# YW_001.net
KiCad netlist of a schematic drawn in Altium Designer
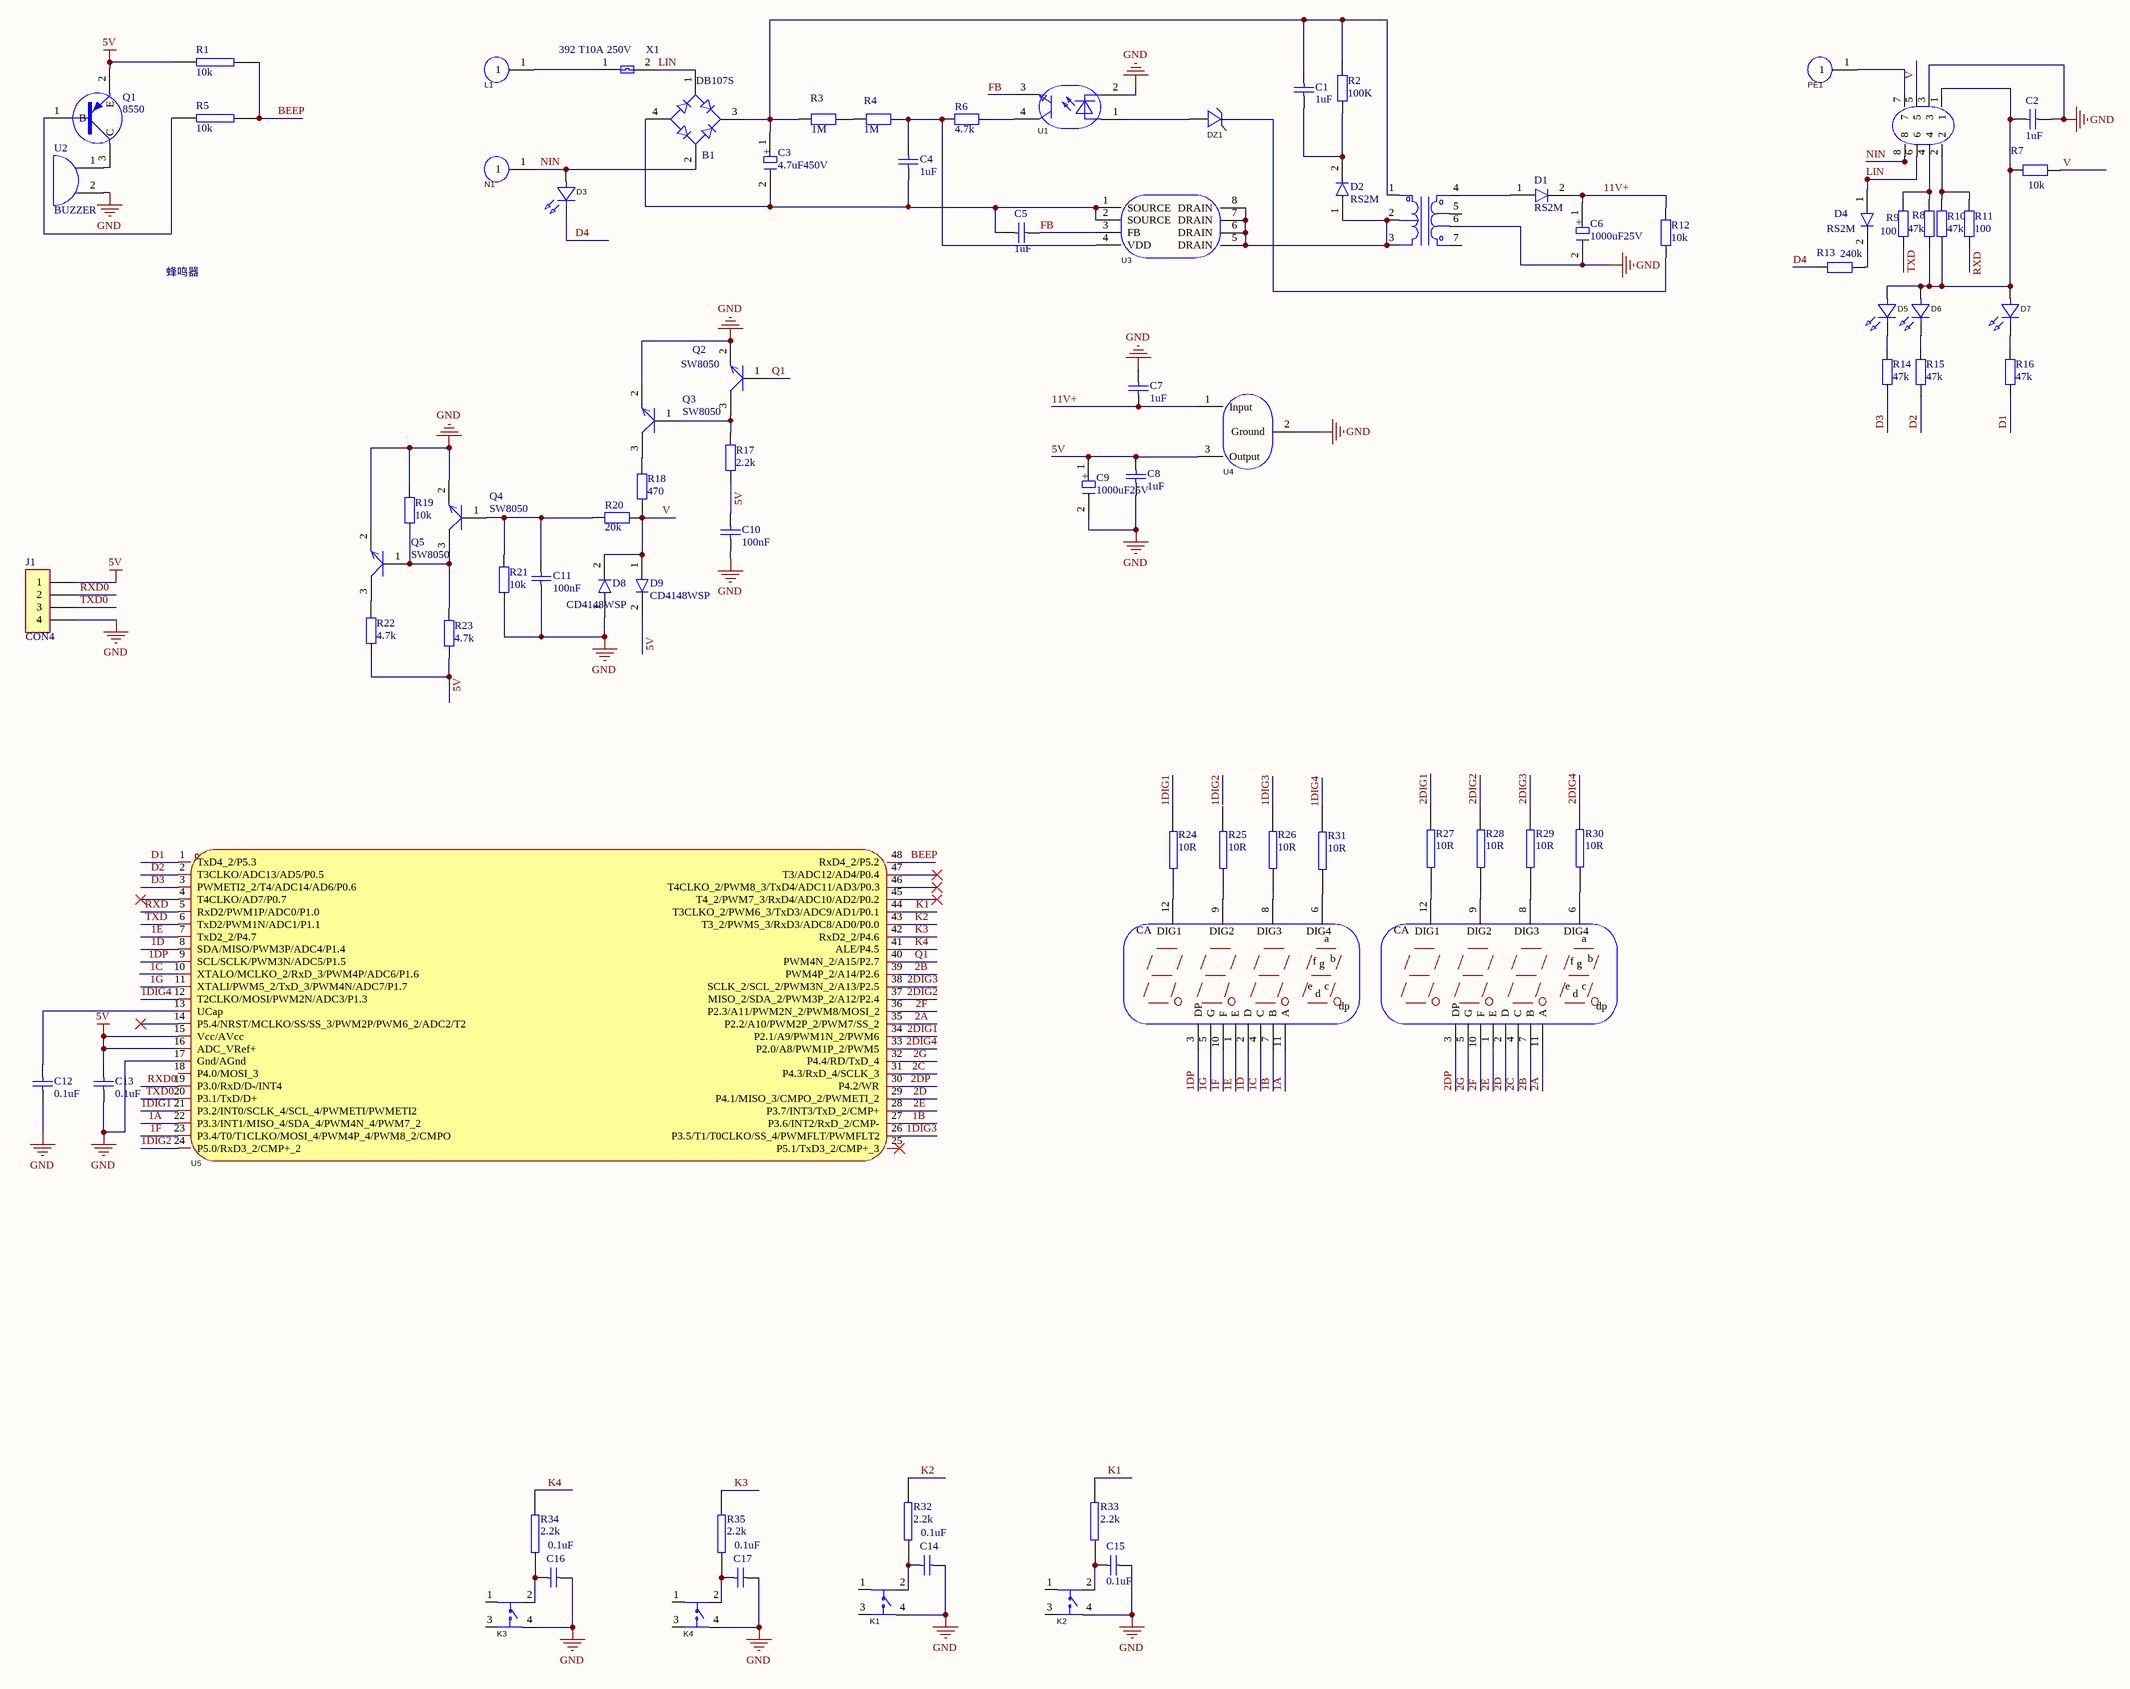
[diagram p0: YW_001.SchDoc]

(export (version "E")
  (design (tool "Eeschema 10.0.6"))
  (components
    (comp (ref "B1") (value "DB107S") (footprint "DB107S") (libsource (lib "*") (part "整流桥堆")))
    (comp (ref "C1")
      (value "1uF")
      (footprint "CAP-TH_L5.5-W4.0-P5.00-D0.5")
      (description "Capacitor")
      (fields (field (name "PUBLISHER") "Altium Limited"))
      (libsource (lib "*") (part "Cap"))
    )
    (comp (ref "C2")
      (value "1uF")
      (footprint "0805C")
      (description "Capacitor")
      (fields (field (name "PUBLISHER") "Altium Limited"))
      (libsource (lib "*") (part "Cap"))
    )
    (comp (ref "C3")
      (value "4.7uF450V")
      (footprint "CAP-TH_BD6.3-P2.50-D1.0-FD")
      (libsource (lib "*") (part "电解电容"))
    )
    (comp (ref "C4")
      (value "1uF")
      (footprint "0805C")
      (description "Capacitor")
      (fields (field (name "PUBLISHER") "Altium Limited"))
      (libsource (lib "*") (part "Cap"))
    )
    (comp (ref "C5")
      (value "1uF")
      (footprint "0805C")
      (description "Capacitor")
      (fields (field (name "PUBLISHER") "Altium Limited"))
      (libsource (lib "*") (part "Cap"))
    )
    (comp (ref "C6")
      (value "1000uF25V")
      (footprint "CAP-TH_BD10.0-P5.00-D1.0-FD")
      (description "CD2881081EM1017VFL")
      (libsource (lib "*") (part "电解电容"))
    )
    (comp (ref "C7")
      (value "1uF")
      (footprint "0805C")
      (description "Capacitor")
      (fields (field (name "PUBLISHER") "Altium Limited"))
      (libsource (lib "*") (part "Cap"))
    )
    (comp (ref "C8")
      (value "1uF")
      (footprint "0805C")
      (description "Capacitor")
      (fields (field (name "PUBLISHER") "Altium Limited"))
      (libsource (lib "*") (part "Cap"))
    )
    (comp (ref "C9")
      (value "1000uF25V")
      (footprint "CAP-TH_BD10.0-P5.00-D1.0-FD")
      (description "CD2881081EM1017VFL")
      (libsource (lib "*") (part "电解电容"))
    )
    (comp (ref "C10")
      (value "100nF")
      (footprint "0805C")
      (description "Capacitor")
      (fields (field (name "PUBLISHER") "Altium Limited"))
      (libsource (lib "*") (part "Cap"))
    )
    (comp (ref "C11")
      (value "100nF")
      (footprint "0805C")
      (description "Capacitor")
      (fields (field (name "PUBLISHER") "Altium Limited"))
      (libsource (lib "*") (part "Cap"))
    )
    (comp (ref "C12")
      (value "0.1uF")
      (footprint "C0603")
      (description "Capacitor")
      (fields (field (name "Comment") "100nF") (field (name "PUBLISHER") "Altium Limited"))
      (libsource (lib "*") (part "Cap"))
    )
    (comp (ref "C13")
      (value "0.1uF")
      (footprint "C0603")
      (description "Capacitor")
      (fields (field (name "Comment") "100nF") (field (name "PUBLISHER") "Altium Limited"))
      (libsource (lib "*") (part "Cap"))
    )
    (comp (ref "C14")
      (value "0.1uF")
      (footprint "0805C")
      (description "Capacitor")
      (fields (field (name "Comment") "104P") (field (name "PUBLISHER") "Altium Limited"))
      (libsource (lib "*") (part "Cap"))
    )
    (comp (ref "C15")
      (value "0.1uF")
      (footprint "0805C")
      (description "Capacitor")
      (fields (field (name "Comment") "104P") (field (name "PUBLISHER") "Altium Limited"))
      (libsource (lib "*") (part "Cap"))
    )
    (comp (ref "C16")
      (value "0.1uF")
      (footprint "0805C")
      (description "Capacitor")
      (fields (field (name "Comment") "104P") (field (name "PUBLISHER") "Altium Limited"))
      (libsource (lib "*") (part "Cap"))
    )
    (comp (ref "C17")
      (value "0.1uF")
      (footprint "0805C")
      (description "Capacitor")
      (fields (field (name "Comment") "104P") (field (name "PUBLISHER") "Altium Limited"))
      (libsource (lib "*") (part "Cap"))
    )
    (comp (ref "D1")
      (value "RS2M")
      (footprint "SMA-SMD_L4.4-W2.7-LS5.4-RD")
      (libsource (lib "CAMERON") (part "二极管"))
    )
    (comp (ref "D2")
      (value "RS2M")
      (footprint "SMA-SMD_L4.4-W2.7-LS5.4-RD")
      (libsource (lib "CAMERON") (part "二极管"))
    )
    (comp (ref "D3")
      (value "HLMP-1503-D0000")
      (footprint "LED-TH_BD3.0-P2.54-RD")
      (fields (field (name "MANUFACTURER") "Broadcom/AVAGO(安华高)"))
      (libsource (lib "CAMERON") (part "HLMP-1503-D0000"))
    )
    (comp (ref "D4")
      (value "RS2M")
      (footprint "SMA-SMD_L4.4-W2.7-LS5.4-RD")
      (libsource (lib "CAMERON") (part "二极管"))
    )
    (comp (ref "D5")
      (value "HLMP-1503-D0000")
      (footprint "LED-TH_BD3.0-P2.54-RD")
      (fields (field (name "MANUFACTURER") "Broadcom/AVAGO(安华高)"))
      (libsource (lib "CAMERON") (part "HLMP-1503-D0000"))
    )
    (comp (ref "D6")
      (value "HLMP-1503-D0000")
      (footprint "LED-TH_BD3.0-P2.54-RD")
      (fields (field (name "MANUFACTURER") "Broadcom/AVAGO(安华高)"))
      (libsource (lib "CAMERON") (part "HLMP-1503-D0000"))
    )
    (comp (ref "D7")
      (value "HLMP-1503-D0000")
      (footprint "LED-TH_BD3.0-P2.54-RD")
      (fields (field (name "MANUFACTURER") "Broadcom/AVAGO(安华高)"))
      (libsource (lib "CAMERON") (part "HLMP-1503-D0000"))
    )
    (comp (ref "D8") (value "CD4148WSP") (footprint "D0805-RD") (libsource (lib "CAMERON") (part "二极管")))
    (comp (ref "D9") (value "CD4148WSP") (footprint "D0805-RD") (libsource (lib "CAMERON") (part "二极管")))
    (comp (ref "DZ1")
      (value "ZMM24")
      (footprint "LL-34_L3.5-W1.5-RD")
      (fields (field (name "MANUFACTURER") "HXY MOSFET(华轩阳电子)"))
      (libsource (lib "CAMERON") (part "ZMM24_C7470923"))
    )
    (comp (ref "H1")
      (value "HC-5557-2*4AW")
      (footprint "CONN-TH_8P-P4.20_5557-2X4AW")
      (fields (field (name "MANUFACTURER") "HCTL(华灿天禄)"))
      (libsource (lib "CAMERON") (part "HC-5557-2*4AW"))
    )
    (comp (ref "J1")
      (value "CON4")
      (footprint "HDR1X4")
      (description "Connector")
      (libsource (lib "*") (part "CON4"))
    )
    (comp (ref "K1")
      (value "TS1212TPFS 250gf 072")
      (footprint "KEY-SMD_4P-L12.0-W12.0-P5.00-LS15.0")
      (fields (field (name "MANUFACTURER") "SHOU HAN(首韩)"))
      (libsource (lib "CAMERON") (part "TS1212TPFS 250gf 072"))
    )
    (comp (ref "K2")
      (value "TS1212TPFS 250gf 072")
      (footprint "KEY-SMD_4P-L12.0-W12.0-P5.00-LS15.0")
      (fields (field (name "MANUFACTURER") "SHOU HAN(首韩)"))
      (libsource (lib "CAMERON") (part "TS1212TPFS 250gf 072"))
    )
    (comp (ref "K3")
      (value "TS1212TPFS 250gf 072")
      (footprint "KEY-SMD_4P-L12.0-W12.0-P5.00-LS15.0")
      (fields (field (name "MANUFACTURER") "SHOU HAN(首韩)"))
      (libsource (lib "CAMERON") (part "TS1212TPFS 250gf 072"))
    )
    (comp (ref "K4")
      (value "TS1212TPFS 250gf 072")
      (footprint "KEY-SMD_4P-L12.0-W12.0-P5.00-LS15.0")
      (fields (field (name "MANUFACTURER") "SHOU HAN(首韩)"))
      (libsource (lib "CAMERON") (part "TS1212TPFS 250gf 072"))
    )
    (comp (ref "L1")
      (value "PZ254V-11-01P")
      (footprint "HDR-TH_1P-P2.54-V-M")
      (fields (field (name "MANUFACTURER") "XFCN(兴飞)"))
      (libsource (lib "CAMERON") (part "PZ254V-11-01P"))
    )
    (comp (ref "LED1")
      (value "FJ5461BH 橙红")
      (footprint "LED-SEG-TH_FJ5461AH")
      (fields (field (name "MANUFACTURER") "志浩"))
      (libsource (lib "CAMERON") (part "FJ5461BH 橙红"))
    )
    (comp (ref "LED2")
      (value "FJ5461BH 橙红")
      (footprint "LED-SEG-TH_FJ5461AH")
      (fields (field (name "MANUFACTURER") "志浩"))
      (libsource (lib "CAMERON") (part "FJ5461BH 橙红"))
    )
    (comp (ref "N1")
      (value "PZ254V-11-01P")
      (footprint "HDR-TH_1P-P2.54-V-M")
      (fields (field (name "MANUFACTURER") "XFCN(兴飞)"))
      (libsource (lib "altium-import") (part "root_2_PZ254V-11-01P_"))
    )
    (comp (ref "PE1")
      (value "PZ254V-11-01P")
      (footprint "HDR-TH_1P-P2.54-V-M")
      (fields (field (name "MANUFACTURER") "XFCN(兴飞)"))
      (libsource (lib "CAMERON") (part "PZ254V-11-01P"))
    )
    (comp (ref "Q1") (value "8550") (footprint "SOT-23") (libsource (lib "*") (part "PNP")))
    (comp (ref "Q2")
      (value "SW8050")
      (footprint "SOT-23 - S8550")
      (libsource (lib "CAMERON") (part "普通三级管（NPN）"))
    )
    (comp (ref "Q3")
      (value "SW8050")
      (footprint "SOT-23 - S8550")
      (libsource (lib "CAMERON") (part "普通三级管（NPN）"))
    )
    (comp (ref "Q4")
      (value "SW8050")
      (footprint "SOT-23 - S8550")
      (libsource (lib "CAMERON") (part "普通三级管（NPN）"))
    )
    (comp (ref "Q5")
      (value "SW8050")
      (footprint "SOT-23 - S8550")
      (libsource (lib "CAMERON") (part "普通三级管（NPN）"))
    )
    (comp (ref "R1") (value "10k") (footprint "0805") (libsource (lib "*") (part "RES2")))
    (comp (ref "R2")
      (value "100K")
      (footprint "0805")
      (description "Resistor")
      (fields (field (name "Comment") "100k") (field (name "PUBLISHER") "Altium Limited"))
      (libsource (lib "") (part "Res2_3"))
    )
    (comp (ref "R3")
      (value "1M")
      (footprint "0805")
      (description "Resistor")
      (fields (field (name "PUBLISHER") "Altium Limited"))
      (libsource (lib "") (part "Res2_2"))
    )
    (comp (ref "R4")
      (value "1M")
      (footprint "0805")
      (description "Resistor")
      (fields (field (name "PUBLISHER") "Altium Limited"))
      (libsource (lib "") (part "Res2_2"))
    )
    (comp (ref "R5") (value "10k") (footprint "0805") (libsource (lib "*") (part "RES2")))
    (comp (ref "R6")
      (value "4.7k")
      (footprint "0805")
      (description "Resistor")
      (fields (field (name "PUBLISHER") "Altium Limited"))
      (libsource (lib "") (part "Res2_2"))
    )
    (comp (ref "R7")
      (value "10k")
      (footprint "0805")
      (description "Resistor")
      (fields (field (name "PUBLISHER") "Altium Limited"))
      (libsource (lib "") (part "Res2_2"))
    )
    (comp (ref "R8")
      (value "47k")
      (footprint "0805")
      (description "Resistor")
      (fields (field (name "PUBLISHER") "Altium Limited"))
      (libsource (lib "") (part "Res2_3"))
    )
    (comp (ref "R9")
      (value "100")
      (footprint "0805")
      (description "Resistor")
      (fields (field (name "PUBLISHER") "Altium Limited"))
      (libsource (lib "*") (part "Res2"))
    )
    (comp (ref "R10")
      (value "47k")
      (footprint "0805")
      (description "Resistor")
      (fields (field (name "PUBLISHER") "Altium Limited"))
      (libsource (lib "") (part "Res2_3"))
    )
    (comp (ref "R11")
      (value "100")
      (footprint "0805")
      (description "Resistor")
      (fields (field (name "PUBLISHER") "Altium Limited"))
      (libsource (lib "*") (part "Res2"))
    )
    (comp (ref "R12")
      (value "10k")
      (footprint "0805")
      (description "Resistor")
      (fields (field (name "PUBLISHER") "Altium Limited"))
      (libsource (lib "") (part "Res2_3"))
    )
    (comp (ref "R13")
      (value "240k")
      (footprint "0805")
      (description "Resistor")
      (fields (field (name "PUBLISHER") "Altium Limited"))
      (libsource (lib "") (part "Res2_2"))
    )
    (comp (ref "R14")
      (value "47k")
      (footprint "0805")
      (description "Resistor")
      (fields (field (name "PUBLISHER") "Altium Limited"))
      (libsource (lib "") (part "Res2_3"))
    )
    (comp (ref "R15")
      (value "47k")
      (footprint "0805")
      (description "Resistor")
      (fields (field (name "PUBLISHER") "Altium Limited"))
      (libsource (lib "") (part "Res2_3"))
    )
    (comp (ref "R16")
      (value "47k")
      (footprint "0805")
      (description "Resistor")
      (fields (field (name "PUBLISHER") "Altium Limited"))
      (libsource (lib "") (part "Res2_3"))
    )
    (comp (ref "R17")
      (value "2.2k")
      (footprint "0805")
      (description "Resistor")
      (fields (field (name "PUBLISHER") "Altium Limited"))
      (libsource (lib "") (part "Res2_3"))
    )
    (comp (ref "R18")
      (value "470")
      (footprint "0805")
      (description "Resistor")
      (fields (field (name "PUBLISHER") "Altium Limited"))
      (libsource (lib "") (part "Res2_3"))
    )
    (comp (ref "R19")
      (value "10k")
      (footprint "0805")
      (description "Resistor")
      (fields (field (name "PUBLISHER") "Altium Limited"))
      (libsource (lib "") (part "Res2_3"))
    )
    (comp (ref "R20")
      (value "20k")
      (footprint "0805")
      (description "Resistor")
      (fields (field (name "PUBLISHER") "Altium Limited"))
      (libsource (lib "") (part "Res2_1"))
    )
    (comp (ref "R21")
      (value "10k")
      (footprint "0805")
      (description "Resistor")
      (fields (field (name "PUBLISHER") "Altium Limited"))
      (libsource (lib "*") (part "Res2"))
    )
    (comp (ref "R22")
      (value "4.7k")
      (footprint "0805")
      (description "Resistor")
      (fields (field (name "PUBLISHER") "Altium Limited"))
      (libsource (lib "") (part "Res2_3"))
    )
    (comp (ref "R23")
      (value "4.7k")
      (footprint "0805")
      (description "Resistor")
      (fields (field (name "PUBLISHER") "Altium Limited"))
      (libsource (lib "") (part "Res2_3"))
    )
    (comp (ref "R24") (value "10R") (footprint "R0603") (libsource (lib "*") (part "RES2")))
    (comp (ref "R25") (value "10R") (footprint "R0603") (libsource (lib "*") (part "RES2")))
    (comp (ref "R26") (value "10R") (footprint "R0603") (libsource (lib "*") (part "RES2")))
    (comp (ref "R27") (value "10R") (footprint "R0603") (libsource (lib "*") (part "RES2")))
    (comp (ref "R28") (value "10R") (footprint "R0603") (libsource (lib "*") (part "RES2")))
    (comp (ref "R29") (value "10R") (footprint "R0603") (libsource (lib "*") (part "RES2")))
    (comp (ref "R30") (value "10R") (footprint "R0603") (libsource (lib "*") (part "RES2")))
    (comp (ref "R31") (value "10R") (footprint "R0603") (libsource (lib "*") (part "RES2")))
    (comp (ref "R32") (value "2.2k") (footprint "0805") (libsource (lib "*") (part "RES2")))
    (comp (ref "R33") (value "2.2k") (footprint "0805") (libsource (lib "*") (part "RES2")))
    (comp (ref "R34") (value "2.2k") (footprint "0805") (libsource (lib "*") (part "RES2")))
    (comp (ref "R35") (value "2.2k") (footprint "0805") (libsource (lib "*") (part "RES2")))
    (comp (ref "U1")
      (value "EL817S1(C)(TU)-F")
      (footprint "OPTO-SMD-4_L4.6-W6.5-P2.54-LS10.3-TL")
      (fields (field (name "MANUFACTURER") "EVERLIGHT(亿光)"))
      (libsource (lib "CAMERON") (part "EL817S1(C)(TU)-F"))
    )
    (comp (ref "U2")
      (value "BUZZER")
      (footprint "BUZZ-7.6/12")
      (description "Buzzer")
      (libsource (lib "*") (part "BUZZER"))
    )
    (comp (ref "U3")
      (value "VIPER12ASTR-E")
      (footprint "SOIC-8_L5.0-W4.0-P1.27-LS6.0-BL")
      (fields (field (name "MANUFACTURER") "ST(意法半导体)"))
      (libsource (lib "CAMERON") (part "VIPER12ASTR-E"))
    )
    (comp (ref "U4")
      (value "MC7805CDTRKG")
      (footprint "TO-252-2_L6.6-W6.1-P4.58-LS9.9-TL")
      (fields (field (name "MANUFACTURER") "onsemi(安森美)"))
      (libsource (lib "CAMERON") (part "MC7805CDTRKG"))
    )
    (comp (ref "U5")
      (value "STC8H8K64U-45I-LQFP48")
      (footprint "LQFP-48_L7.0-W7.0-P0.50-LS9.0-BL")
      (fields (field (name "MANUFACTURER") "STC(宏晶)"))
      (libsource (lib "CAMERON") (part "STC8H8K64U-45I-LQFP48"))
    )
    (comp (ref "USB1")
      (value "ECO2017SEO-X16V015")
      (footprint "XFMR-TH_ECO2017SEO-X16V015")
      (fields (field (name "MANUFACTURER") "TDK"))
      (libsource (lib "CAMERON") (part "ECO2017SEO-X16V015"))
    )
    (comp (ref "X1") (value "392 T10A 250V") (footprint "FUSE") (libsource (lib "*") (part "保险丝")))
  )
  (nets
    (net (code "1") (name "/1A") (class "Default")
      (node (ref "LED1") (pin "11") (pinfunction "A_11") (pintype "passive"))
      (node (ref "U5") (pin "22") (pinfunction "P3.3/INT1/MISO_4/SDA_4/PWM4N_4/PWM7_2_22") (pintype "passive"))
    )
    (net (code "2") (name "/1B") (class "Default")
      (node (ref "LED1") (pin "7") (pinfunction "B_7") (pintype "passive"))
      (node (ref "U5") (pin "27") (pinfunction "P3.6/INT2/RxD_2/CMP-_27") (pintype "passive"))
    )
    (net (code "3") (name "/1C") (class "Default")
      (node (ref "LED1") (pin "4") (pinfunction "C_4") (pintype "passive"))
      (node (ref "U5") (pin "10") (pinfunction "XTALO/MCLKO_2/RxD_3/PWM4P/ADC6/P1.6_10") (pintype "passive"))
    )
    (net (code "4") (name "/1D") (class "Default")
      (node (ref "LED1") (pin "2") (pinfunction "D_2") (pintype "passive"))
      (node (ref "U5") (pin "8") (pinfunction "SDA/MISO/PWM3P/ADC4/P1.4_8") (pintype "passive"))
    )
    (net (code "5") (name "/1DIG1") (class "Default")
      (node (ref "R24") (pin "1") (pinfunction "1_1") (pintype "passive"))
      (node (ref "U5") (pin "21") (pinfunction "P3.2/INT0/SCLK_4/SCL_4/PWMETI/PWMETI2_21") (pintype "passive"))
    )
    (net (code "6") (name "/1DIG2") (class "Default")
      (node (ref "R25") (pin "1") (pinfunction "1_1") (pintype "passive"))
      (node (ref "U5") (pin "24") (pinfunction "P5.0/RxD3_2/CMP+_2_24") (pintype "passive"))
    )
    (net (code "7") (name "/1DIG3") (class "Default")
      (node (ref "R26") (pin "1") (pinfunction "1_1") (pintype "passive"))
      (node (ref "U5") (pin "26") (pinfunction "P3.5/T1/T0CLKO/SS_4/PWMFLT/PWMFLT2_26") (pintype "passive"))
    )
    (net (code "8") (name "/1DIG4") (class "Default")
      (node (ref "R31") (pin "2") (pinfunction "2_2") (pintype "passive"))
      (node (ref "U5") (pin "12") (pinfunction "T2CLKO/MOSI/PWM2N/ADC3/P1.3_12") (pintype "passive"))
    )
    (net (code "9") (name "/1DP") (class "Default")
      (node (ref "LED1") (pin "3") (pinfunction "DP_3") (pintype "passive"))
      (node (ref "U5") (pin "9") (pinfunction "SCL/SCLK/PWM3N/ADC5/P1.5_9") (pintype "passive"))
    )
    (net (code "10") (name "/1E") (class "Default")
      (node (ref "LED1") (pin "1") (pinfunction "E_1") (pintype "passive"))
      (node (ref "U5") (pin "7") (pinfunction "TxD2_2/P4.7_7") (pintype "passive"))
    )
    (net (code "11") (name "/1F") (class "Default")
      (node (ref "LED1") (pin "10") (pinfunction "F_10") (pintype "passive"))
      (node (ref "U5") (pin "23") (pinfunction "P3.4/T0/T1CLKO/MOSI_4/PWM4P_4/PWM8_2/CMPO_23") (pintype "passive"))
    )
    (net (code "12") (name "/1G") (class "Default")
      (node (ref "LED1") (pin "5") (pinfunction "G_5") (pintype "passive"))
      (node (ref "U5") (pin "11") (pinfunction "XTALI/PWM5_2/TxD_3/PWM4N/ADC7/P1.7_11") (pintype "passive"))
    )
    (net (code "13") (name "/2A") (class "Default")
      (node (ref "LED2") (pin "11") (pinfunction "A_11") (pintype "passive"))
      (node (ref "U5") (pin "35") (pinfunction "P2.2/A10/PWM2P_2/PWM7/SS_2_35") (pintype "passive"))
    )
    (net (code "14") (name "/2B") (class "Default")
      (node (ref "LED2") (pin "7") (pinfunction "B_7") (pintype "passive"))
      (node (ref "U5") (pin "39") (pinfunction "PWM4P_2/A14/P2.6_39") (pintype "passive"))
    )
    (net (code "15") (name "/2C") (class "Default")
      (node (ref "LED2") (pin "4") (pinfunction "C_4") (pintype "passive"))
      (node (ref "U5") (pin "31") (pinfunction "P4.3/RxD_4/SCLK_3_31") (pintype "passive"))
    )
    (net (code "16") (name "/2D") (class "Default")
      (node (ref "LED2") (pin "2") (pinfunction "D_2") (pintype "passive"))
      (node (ref "U5") (pin "29") (pinfunction "P4.1/MISO_3/CMPO_2/PWMETI_2_29") (pintype "passive"))
    )
    (net (code "17") (name "/2DIG1") (class "Default")
      (node (ref "R27") (pin "1") (pinfunction "1_1") (pintype "passive"))
      (node (ref "U5") (pin "34") (pinfunction "P2.1/A9/PWM1N_2/PWM6_34") (pintype "passive"))
    )
    (net (code "18") (name "/2DIG2") (class "Default")
      (node (ref "R28") (pin "1") (pinfunction "1_1") (pintype "passive"))
      (node (ref "U5") (pin "37") (pinfunction "MISO_2/SDA_2/PWM3P_2/A12/P2.4_37") (pintype "passive"))
    )
    (net (code "19") (name "/2DIG3") (class "Default")
      (node (ref "R29") (pin "1") (pinfunction "1_1") (pintype "passive"))
      (node (ref "U5") (pin "38") (pinfunction "SCLK_2/SCL_2/PWM3N_2/A13/P2.5_38") (pintype "passive"))
    )
    (net (code "20") (name "/2DIG4") (class "Default")
      (node (ref "R30") (pin "2") (pinfunction "2_2") (pintype "passive"))
      (node (ref "U5") (pin "33") (pinfunction "P2.0/A8/PWM1P_2/PWM5_33") (pintype "passive"))
    )
    (net (code "21") (name "/2DP") (class "Default")
      (node (ref "LED2") (pin "3") (pinfunction "DP_3") (pintype "passive"))
      (node (ref "U5") (pin "30") (pinfunction "P4.2/WR_30") (pintype "passive"))
    )
    (net (code "22") (name "/2E") (class "Default")
      (node (ref "LED2") (pin "1") (pinfunction "E_1") (pintype "passive"))
      (node (ref "U5") (pin "28") (pinfunction "P3.7/INT3/TxD_2/CMP+_28") (pintype "passive"))
    )
    (net (code "23") (name "/2F") (class "Default")
      (node (ref "LED2") (pin "10") (pinfunction "F_10") (pintype "passive"))
      (node (ref "U5") (pin "36") (pinfunction "P2.3/A11/PWM2N_2/PWM8/MOSI_2_36") (pintype "passive"))
    )
    (net (code "24") (name "/2G") (class "Default")
      (node (ref "LED2") (pin "5") (pinfunction "G_5") (pintype "passive"))
      (node (ref "U5") (pin "32") (pinfunction "P4.4/RD/TxD_4_32") (pintype "passive"))
    )
    (net (code "25") (name "/11V+") (class "Default")
      (node (ref "C6") (pin "1") (pintype "passive"))
      (node (ref "C7") (pin "2") (pinfunction "2_2") (pintype "passive"))
      (node (ref "D1") (pin "2") (pintype "passive"))
      (node (ref "R12") (pin "1") (pinfunction "1_1") (pintype "passive"))
      (node (ref "U4") (pin "1") (pinfunction "Input_1") (pintype "passive"))
    )
    (net (code "26") (name "/BEEP") (class "Default")
      (node (ref "R1") (pin "2") (pinfunction "2_2") (pintype "passive"))
      (node (ref "R5") (pin "2") (pinfunction "2_2") (pintype "passive"))
      (node (ref "U5") (pin "48") (pinfunction "RxD4_2/P5.2_48") (pintype "passive"))
    )
    (net (code "27") (name "/D1") (class "Default")
      (node (ref "R16") (pin "2") (pinfunction "2_2") (pintype "passive"))
      (node (ref "U5") (pin "1") (pinfunction "TxD4_2/P5.3_1") (pintype "passive"))
    )
    (net (code "28") (name "/D2") (class "Default")
      (node (ref "R15") (pin "2") (pinfunction "2_2") (pintype "passive"))
      (node (ref "U5") (pin "2") (pinfunction "T3CLKO/ADC13/AD5/P0.5_2") (pintype "passive"))
    )
    (net (code "29") (name "/D3") (class "Default")
      (node (ref "R14") (pin "2") (pinfunction "2_2") (pintype "passive"))
      (node (ref "U5") (pin "3") (pinfunction "PWMETI2_2/T4/ADC14/AD6/P0.6_3") (pintype "passive"))
    )
    (net (code "30") (name "/D4") (class "Default")
      (node (ref "D3") (pin "1") (pinfunction "K_1") (pintype "passive"))
      (node (ref "R13") (pin "2") (pinfunction "2_2") (pintype "passive"))
    )
    (net (code "31") (name "/FB") (class "Default")
      (node (ref "C5") (pin "1") (pinfunction "1_1") (pintype "passive"))
      (node (ref "U1") (pin "3") (pinfunction "EM_3") (pintype "passive"))
      (node (ref "U3") (pin "3") (pinfunction "FB_3") (pintype "passive"))
    )
    (net (code "32") (name "/K1") (class "Default")
      (node (ref "R33") (pin "2") (pinfunction "2_2") (pintype "passive"))
      (node (ref "U5") (pin "44") (pinfunction "T3CLKO_2/PWM6_3/TxD3/ADC9/AD1/P0.1_44") (pintype "passive"))
    )
    (net (code "33") (name "/K2") (class "Default")
      (node (ref "R32") (pin "2") (pinfunction "2_2") (pintype "passive"))
      (node (ref "U5") (pin "43") (pinfunction "T3_2/PWM5_3/RxD3/ADC8/AD0/P0.0_43") (pintype "passive"))
    )
    (net (code "34") (name "/K3") (class "Default")
      (node (ref "R35") (pin "2") (pinfunction "2_2") (pintype "passive"))
      (node (ref "U5") (pin "42") (pinfunction "RxD2_2/P4.6_42") (pintype "passive"))
    )
    (net (code "35") (name "/K4") (class "Default")
      (node (ref "R34") (pin "2") (pinfunction "2_2") (pintype "passive"))
      (node (ref "U5") (pin "41") (pinfunction "ALE/P4.5_41") (pintype "passive"))
    )
    (net (code "36") (name "/LIN") (class "Default")
      (node (ref "B1") (pin "1") (pintype "passive"))
      (node (ref "D4") (pin "1") (pintype "passive"))
      (node (ref "H1") (pin "6") (pinfunction "6_6") (pintype "passive"))
      (node (ref "X1") (pin "2") (pintype "passive"))
    )
    (net (code "37") (name "/NIN") (class "Default")
      (node (ref "B1") (pin "2") (pintype "passive"))
      (node (ref "D3") (pin "2") (pinfunction "A_2") (pintype "passive"))
      (node (ref "H1") (pin "8") (pinfunction "8_8") (pintype "passive"))
      (node (ref "N1") (pin "1") (pinfunction "1_1") (pintype "passive"))
    )
    (net (code "38") (name "/Q1") (class "Default")
      (node (ref "Q2") (pin "1") (pinfunction "B_1") (pintype "passive"))
      (node (ref "U5") (pin "40") (pinfunction "PWM4N_2/A15/P2.7_40") (pintype "passive"))
    )
    (net (code "39") (name "/RXD") (class "Default")
      (node (ref "R11") (pin "1") (pinfunction "1_1") (pintype "passive"))
      (node (ref "U5") (pin "5") (pinfunction "RxD2/PWM1P/ADC0/P1.0_5") (pintype "passive"))
    )
    (net (code "40") (name "/RXD0") (class "Default")
      (node (ref "J1") (pin "2") (pinfunction "2_2") (pintype "passive"))
      (node (ref "U5") (pin "19") (pinfunction "P3.0/RxD/D-/INT4_19") (pintype "passive"))
    )
    (net (code "41") (name "/TXD") (class "Default")
      (node (ref "R9") (pin "1") (pinfunction "1_1") (pintype "passive"))
      (node (ref "U5") (pin "6") (pinfunction "TxD2/PWM1N/ADC1/P1.1_6") (pintype "passive"))
    )
    (net (code "42") (name "/TXD0") (class "Default")
      (node (ref "J1") (pin "3") (pinfunction "3_3") (pintype "passive"))
      (node (ref "U5") (pin "20") (pinfunction "P3.1/TxD/D+_20") (pintype "passive"))
    )
    (net (code "43") (name "/V") (class "Default")
      (node (ref "D8") (pin "2") (pintype "passive"))
      (node (ref "D9") (pin "1") (pintype "passive"))
      (node (ref "H1") (pin "5") (pinfunction "5_5") (pintype "passive"))
      (node (ref "R18") (pin "2") (pinfunction "2_2") (pintype "passive"))
      (node (ref "R20") (pin "2") (pinfunction "2_2") (pintype "passive"))
      (node (ref "R7") (pin "1") (pinfunction "1_1") (pintype "passive"))
    )
    (net (code "44") (name "5V") (class "Default")
      (node (ref "C10") (pin "1") (pinfunction "1_1") (pintype "passive"))
      (node (ref "C13") (pin "2") (pinfunction "2_2") (pintype "passive"))
      (node (ref "C8") (pin "1") (pinfunction "1_1") (pintype "passive"))
      (node (ref "C9") (pin "1") (pintype "passive"))
      (node (ref "D9") (pin "2") (pintype "passive"))
      (node (ref "J1") (pin "1") (pinfunction "1_1") (pintype "passive"))
      (node (ref "Q1") (pin "2") (pinfunction "E_2") (pintype "passive"))
      (node (ref "R1") (pin "1") (pinfunction "1_1") (pintype "passive"))
      (node (ref "R17") (pin "2") (pinfunction "2_2") (pintype "passive"))
      (node (ref "R22") (pin "2") (pinfunction "2_2") (pintype "passive"))
      (node (ref "R23") (pin "2") (pinfunction "2_2") (pintype "passive"))
      (node (ref "U4") (pin "3") (pinfunction "Output_3") (pintype "passive"))
      (node (ref "U5") (pin "15") (pinfunction "Vcc/AVcc_15") (pintype "passive"))
      (node (ref "U5") (pin "16") (pinfunction "ADC_VRef+_16") (pintype "passive"))
    )
    (net (code "45") (name "GND") (class "Default")
      (node (ref "C10") (pin "2") (pinfunction "2_2") (pintype "passive"))
      (node (ref "C11") (pin "2") (pinfunction "2_2") (pintype "passive"))
      (node (ref "C12") (pin "1") (pinfunction "1_1") (pintype "passive"))
      (node (ref "C13") (pin "1") (pinfunction "1_1") (pintype "passive"))
      (node (ref "C14") (pin "2") (pinfunction "2_2") (pintype "passive"))
      (node (ref "C15") (pin "2") (pinfunction "2_2") (pintype "passive"))
      (node (ref "C16") (pin "2") (pinfunction "2_2") (pintype "passive"))
      (node (ref "C17") (pin "2") (pinfunction "2_2") (pintype "passive"))
      (node (ref "C2") (pin "1") (pinfunction "1_1") (pintype "passive"))
      (node (ref "C6") (pin "2") (pintype "passive"))
      (node (ref "C7") (pin "1") (pinfunction "1_1") (pintype "passive"))
      (node (ref "C8") (pin "2") (pinfunction "2_2") (pintype "passive"))
      (node (ref "C9") (pin "2") (pintype "passive"))
      (node (ref "D8") (pin "1") (pintype "passive"))
      (node (ref "H1") (pin "3") (pinfunction "3_3") (pintype "passive"))
      (node (ref "J1") (pin "4") (pinfunction "4_4") (pintype "passive"))
      (node (ref "K1") (pin "4") (pinfunction "4_4") (pintype "passive"))
      (node (ref "K2") (pin "4") (pinfunction "4_4") (pintype "passive"))
      (node (ref "K3") (pin "4") (pinfunction "4_4") (pintype "passive"))
      (node (ref "K4") (pin "4") (pinfunction "4_4") (pintype "passive"))
      (node (ref "Q2") (pin "2") (pinfunction "E_2") (pintype "passive"))
      (node (ref "Q3") (pin "2") (pinfunction "E_2") (pintype "passive"))
      (node (ref "Q4") (pin "2") (pinfunction "E_2") (pintype "passive"))
      (node (ref "Q5") (pin "2") (pinfunction "E_2") (pintype "passive"))
      (node (ref "R19") (pin "1") (pinfunction "1_1") (pintype "passive"))
      (node (ref "R21") (pin "1") (pinfunction "1_1") (pintype "passive"))
      (node (ref "U1") (pin "2") (pinfunction "CAT_2") (pintype "passive"))
      (node (ref "U2") (pin "2") (pinfunction "B_2") (pintype "passive"))
      (node (ref "U4") (pin "2") (pinfunction "Ground_2") (pintype "passive"))
      (node (ref "U5") (pin "17") (pinfunction "Gnd/AGnd_17") (pintype "passive"))
      (node (ref "USB1") (pin "6") (pinfunction "2_6") (pintype "passive"))
    )
    (net (code "46") (name "Net-(B1-Pad4)") (class "Default")
      (node (ref "B1") (pin "4") (pintype "passive"))
      (node (ref "C3") (pin "2") (pintype "passive"))
      (node (ref "C4") (pin "2") (pinfunction "2_2") (pintype "passive"))
      (node (ref "C5") (pin "2") (pinfunction "2_2") (pintype "passive"))
      (node (ref "U3") (pin "1") (pinfunction "SOURCE_1") (pintype "passive"))
      (node (ref "U3") (pin "2") (pinfunction "SOURCE_2") (pintype "passive"))
    )
    (net (code "47") (name "Net-(C1-Pad2)") (class "Default")
      (node (ref "C1") (pin "2") (pinfunction "2_2") (pintype "passive"))
      (node (ref "D2") (pin "2") (pintype "passive"))
      (node (ref "R2") (pin "2") (pinfunction "2_2") (pintype "passive"))
    )
    (net (code "48") (name "Net-(C14-Pad1)") (class "Default")
      (node (ref "C14") (pin "1") (pinfunction "1_1") (pintype "passive"))
      (node (ref "K1") (pin "2") (pinfunction "2_2") (pintype "passive"))
      (node (ref "R32") (pin "1") (pinfunction "1_1") (pintype "passive"))
    )
    (net (code "49") (name "Net-(C15-Pad1)") (class "Default")
      (node (ref "C15") (pin "1") (pinfunction "1_1") (pintype "passive"))
      (node (ref "K2") (pin "2") (pinfunction "2_2") (pintype "passive"))
      (node (ref "R33") (pin "1") (pinfunction "1_1") (pintype "passive"))
    )
    (net (code "50") (name "Net-(C16-Pad1)") (class "Default")
      (node (ref "C16") (pin "1") (pinfunction "1_1") (pintype "passive"))
      (node (ref "K3") (pin "2") (pinfunction "2_2") (pintype "passive"))
      (node (ref "R34") (pin "1") (pinfunction "1_1") (pintype "passive"))
    )
    (net (code "51") (name "Net-(C17-Pad1)") (class "Default")
      (node (ref "C17") (pin "1") (pinfunction "1_1") (pintype "passive"))
      (node (ref "K4") (pin "2") (pinfunction "2_2") (pintype "passive"))
      (node (ref "R35") (pin "1") (pinfunction "1_1") (pintype "passive"))
    )
    (net (code "52") (name "Net-(D4-Pad2)") (class "Default")
      (node (ref "D4") (pin "2") (pintype "passive"))
      (node (ref "R13") (pin "1") (pinfunction "1_1") (pintype "passive"))
    )
    (net (code "53") (name "Net-(D5-A)") (class "Default")
      (node (ref "C2") (pin "2") (pinfunction "2_2") (pintype "passive"))
      (node (ref "D5") (pin "2") (pinfunction "A_2") (pintype "passive"))
      (node (ref "D6") (pin "2") (pinfunction "A_2") (pintype "passive"))
      (node (ref "D7") (pin "2") (pinfunction "A_2") (pintype "passive"))
      (node (ref "H1") (pin "1") (pinfunction "1_1") (pintype "passive"))
      (node (ref "R10") (pin "2") (pinfunction "2_2") (pintype "passive"))
      (node (ref "R7") (pin "2") (pinfunction "2_2") (pintype "passive"))
      (node (ref "R8") (pin "2") (pinfunction "2_2") (pintype "passive"))
    )
    (net (code "54") (name "Net-(D5-K)") (class "Default")
      (node (ref "D5") (pin "1") (pinfunction "K_1") (pintype "passive"))
      (node (ref "R14") (pin "1") (pinfunction "1_1") (pintype "passive"))
    )
    (net (code "55") (name "Net-(D6-K)") (class "Default")
      (node (ref "D6") (pin "1") (pinfunction "K_1") (pintype "passive"))
      (node (ref "R15") (pin "1") (pinfunction "1_1") (pintype "passive"))
    )
    (net (code "56") (name "Net-(D7-K)") (class "Default")
      (node (ref "D7") (pin "1") (pinfunction "K_1") (pintype "passive"))
      (node (ref "R16") (pin "1") (pinfunction "1_1") (pintype "passive"))
    )
    (net (code "57") (name "Net-(DZ1-A)") (class "Default")
      (node (ref "DZ1") (pin "2") (pinfunction "A_2") (pintype "passive"))
      (node (ref "U1") (pin "1") (pinfunction "AN_1") (pintype "passive"))
    )
    (net (code "58") (name "Net-(DZ1-C)") (class "Default")
      (node (ref "DZ1") (pin "1") (pinfunction "C_1") (pintype "passive"))
      (node (ref "R12") (pin "2") (pinfunction "2_2") (pintype "passive"))
    )
    (net (code "59") (name "Net-(H1-Pad2)") (class "Default")
      (node (ref "H1") (pin "2") (pinfunction "2_2") (pintype "passive"))
      (node (ref "R10") (pin "1") (pinfunction "1_1") (pintype "passive"))
      (node (ref "R11") (pin "2") (pinfunction "2_2") (pintype "passive"))
    )
    (net (code "60") (name "Net-(H1-Pad4)") (class "Default")
      (node (ref "H1") (pin "4") (pinfunction "4_4") (pintype "passive"))
      (node (ref "R8") (pin "1") (pinfunction "1_1") (pintype "passive"))
      (node (ref "R9") (pin "2") (pinfunction "2_2") (pintype "passive"))
    )
    (net (code "61") (name "Net-(H1-Pad7)") (class "Default")
      (node (ref "H1") (pin "7") (pinfunction "7_7") (pintype "passive"))
      (node (ref "PE1") (pin "1") (pinfunction "1_1") (pintype "passive"))
    )
    (net (code "62") (name "Net-(L1-Pad1)") (class "Default")
      (node (ref "L1") (pin "1") (pinfunction "1_1") (pintype "passive"))
      (node (ref "X1") (pin "1") (pintype "passive"))
    )
    (net (code "63") (name "Net-(LED1-DIG1)") (class "Default")
      (node (ref "LED1") (pin "12") (pinfunction "DIG1_12") (pintype "passive"))
      (node (ref "R24") (pin "2") (pinfunction "2_2") (pintype "passive"))
    )
    (net (code "64") (name "Net-(LED1-DIG2)") (class "Default")
      (node (ref "LED1") (pin "9") (pinfunction "DIG2_9") (pintype "passive"))
      (node (ref "R25") (pin "2") (pinfunction "2_2") (pintype "passive"))
    )
    (net (code "65") (name "Net-(LED1-DIG3)") (class "Default")
      (node (ref "LED1") (pin "8") (pinfunction "DIG3_8") (pintype "passive"))
      (node (ref "R26") (pin "2") (pinfunction "2_2") (pintype "passive"))
    )
    (net (code "66") (name "Net-(LED1-DIG4)") (class "Default")
      (node (ref "LED1") (pin "6") (pinfunction "DIG4_6") (pintype "passive"))
      (node (ref "R31") (pin "1") (pinfunction "1_1") (pintype "passive"))
    )
    (net (code "67") (name "Net-(LED2-DIG1)") (class "Default")
      (node (ref "LED2") (pin "12") (pinfunction "DIG1_12") (pintype "passive"))
      (node (ref "R27") (pin "2") (pinfunction "2_2") (pintype "passive"))
    )
    (net (code "68") (name "Net-(LED2-DIG2)") (class "Default")
      (node (ref "LED2") (pin "9") (pinfunction "DIG2_9") (pintype "passive"))
      (node (ref "R28") (pin "2") (pinfunction "2_2") (pintype "passive"))
    )
    (net (code "69") (name "Net-(LED2-DIG3)") (class "Default")
      (node (ref "LED2") (pin "8") (pinfunction "DIG3_8") (pintype "passive"))
      (node (ref "R29") (pin "2") (pinfunction "2_2") (pintype "passive"))
    )
    (net (code "70") (name "Net-(LED2-DIG4)") (class "Default")
      (node (ref "LED2") (pin "6") (pinfunction "DIG4_6") (pintype "passive"))
      (node (ref "R30") (pin "1") (pinfunction "1_1") (pintype "passive"))
    )
    (net (code "71") (name "Net-(Q1-B)") (class "Default")
      (node (ref "Q1") (pin "1") (pinfunction "B_1") (pintype "passive"))
      (node (ref "R5") (pin "1") (pinfunction "1_1") (pintype "passive"))
    )
    (net (code "72") (name "Net-(Q1-C)") (class "Default")
      (node (ref "Q1") (pin "3") (pinfunction "C_3") (pintype "passive"))
      (node (ref "U2") (pin "1") (pinfunction "A_1") (pintype "passive"))
    )
    (net (code "73") (name "Net-(Q2-C)") (class "Default")
      (node (ref "Q2") (pin "3") (pinfunction "C_3") (pintype "passive"))
      (node (ref "Q3") (pin "1") (pinfunction "B_1") (pintype "passive"))
      (node (ref "R17") (pin "1") (pinfunction "1_1") (pintype "passive"))
    )
    (net (code "74") (name "Net-(Q3-C)") (class "Default")
      (node (ref "Q3") (pin "3") (pinfunction "C_3") (pintype "passive"))
      (node (ref "R18") (pin "1") (pinfunction "1_1") (pintype "passive"))
    )
    (net (code "75") (name "Net-(Q4-B)") (class "Default")
      (node (ref "C11") (pin "1") (pinfunction "1_1") (pintype "passive"))
      (node (ref "Q4") (pin "1") (pinfunction "B_1") (pintype "passive"))
      (node (ref "R20") (pin "1") (pinfunction "1_1") (pintype "passive"))
      (node (ref "R21") (pin "2") (pinfunction "2_2") (pintype "passive"))
    )
    (net (code "76") (name "Net-(Q4-C)") (class "Default")
      (node (ref "Q4") (pin "3") (pinfunction "C_3") (pintype "passive"))
      (node (ref "Q5") (pin "1") (pinfunction "B_1") (pintype "passive"))
      (node (ref "R19") (pin "2") (pinfunction "2_2") (pintype "passive"))
      (node (ref "R23") (pin "1") (pinfunction "1_1") (pintype "passive"))
    )
    (net (code "77") (name "Net-(Q5-C)") (class "Default")
      (node (ref "Q5") (pin "3") (pinfunction "C_3") (pintype "passive"))
      (node (ref "R22") (pin "1") (pinfunction "1_1") (pintype "passive"))
    )
    (net (code "78") (name "Net-(R3-Pad1)") (class "Default")
      (node (ref "R3") (pin "1") (pinfunction "1_1") (pintype "passive"))
      (node (ref "R4") (pin "2") (pinfunction "2_2") (pintype "passive"))
    )
    (net (code "79") (name "Net-(U1-COL)") (class "Default")
      (node (ref "R6") (pin "1") (pinfunction "1_1") (pintype "passive"))
      (node (ref "U1") (pin "4") (pinfunction "COL_4") (pintype "passive"))
    )
    (net (code "80") (name "Net-(U3-VDD)") (class "Default")
      (node (ref "C4") (pin "1") (pinfunction "1_1") (pintype "passive"))
      (node (ref "R4") (pin "1") (pinfunction "1_1") (pintype "passive"))
      (node (ref "R6") (pin "2") (pinfunction "2_2") (pintype "passive"))
      (node (ref "U3") (pin "4") (pinfunction "VDD_4") (pintype "passive"))
    )
    (net (code "81") (name "Net-(U5-UCap)") (class "Default")
      (node (ref "C12") (pin "2") (pinfunction "2_2") (pintype "passive"))
      (node (ref "U5") (pin "13") (pinfunction "UCap_13") (pintype "passive"))
    )
    (net (code "82") (name "Net-(USB1-5)") (class "Default")
      (node (ref "D1") (pin "1") (pintype "passive"))
      (node (ref "USB1") (pin "4") (pinfunction "5_4") (pintype "passive"))
    )
    (net (code "83") (name "Net-(USB1-9)") (class "Default")
      (node (ref "B1") (pin "3") (pintype "passive"))
      (node (ref "C1") (pin "1") (pinfunction "1_1") (pintype "passive"))
      (node (ref "C3") (pin "1") (pintype "passive"))
      (node (ref "R2") (pin "1") (pinfunction "1_1") (pintype "passive"))
      (node (ref "R3") (pin "2") (pinfunction "2_2") (pintype "passive"))
      (node (ref "USB1") (pin "1") (pinfunction "9_1") (pintype "passive"))
    )
    (net (code "84") (name "Net-(USB1-10)") (class "Default")
      (node (ref "D2") (pin "1") (pintype "passive"))
      (node (ref "U3") (pin "5") (pinfunction "DRAIN_5") (pintype "passive"))
      (node (ref "U3") (pin "6") (pinfunction "DRAIN_6") (pintype "passive"))
      (node (ref "U3") (pin "7") (pinfunction "DRAIN_7") (pintype "passive"))
      (node (ref "U3") (pin "8") (pinfunction "DRAIN_8") (pintype "passive"))
      (node (ref "USB1") (pin "2") (pinfunction "8_2") (pintype "passive"))
      (node (ref "USB1") (pin "3") (pinfunction "10_3") (pintype "passive"))
    )
    (net (code "85") (name "unconnected-(K1-Pad1)") (class "Default")
      (node (ref "K1") (pin "1") (pinfunction "1_1") (pintype "passive"))
    )
    (net (code "86") (name "unconnected-(K1-Pad3)") (class "Default")
      (node (ref "K1") (pin "3") (pinfunction "3_3") (pintype "passive"))
    )
    (net (code "87") (name "unconnected-(K2-Pad1)") (class "Default")
      (node (ref "K2") (pin "1") (pinfunction "1_1") (pintype "passive"))
    )
    (net (code "88") (name "unconnected-(K2-Pad3)") (class "Default")
      (node (ref "K2") (pin "3") (pinfunction "3_3") (pintype "passive"))
    )
    (net (code "89") (name "unconnected-(K3-Pad1)") (class "Default")
      (node (ref "K3") (pin "1") (pinfunction "1_1") (pintype "passive"))
    )
    (net (code "90") (name "unconnected-(K3-Pad3)") (class "Default")
      (node (ref "K3") (pin "3") (pinfunction "3_3") (pintype "passive"))
    )
    (net (code "91") (name "unconnected-(K4-Pad1)") (class "Default")
      (node (ref "K4") (pin "1") (pinfunction "1_1") (pintype "passive"))
    )
    (net (code "92") (name "unconnected-(K4-Pad3)") (class "Default")
      (node (ref "K4") (pin "3") (pinfunction "3_3") (pintype "passive"))
    )
    (net (code "93") (name "unconnected-(U5-P4.0{slash}MOSI_3-Pad18)") (class "Default")
      (node (ref "U5") (pin "18") (pinfunction "P4.0/MOSI_3_18") (pintype "passive"))
    )
    (net (code "94") (name "unconnected-(U5-P5.1{slash}TxD3_2{slash}CMP+_3-Pad25)") (class "Default")
      (node (ref "U5") (pin "25") (pinfunction "P5.1/TxD3_2/CMP+_3_25") (pintype "passive+no_connect"))
    )
    (net (code "95") (name "unconnected-(U5-P5.4{slash}NRST{slash}MCLKO{slash}SS{slash}SS_3{slash}PWM2P{slash}PWM6_2{slash}ADC2{slash}T2-Pad14)") (class "Default")
      (node (ref "U5") (pin "14") (pinfunction "P5.4/NRST/MCLKO/SS/SS_3/PWM2P/PWM6_2/ADC2/T2_14") (pintype "passive+no_connect"))
    )
    (net (code "96") (name "unconnected-(U5-T3{slash}ADC12{slash}AD4{slash}P0.4-Pad47)") (class "Default")
      (node (ref "U5") (pin "47") (pinfunction "T3/ADC12/AD4/P0.4_47") (pintype "passive+no_connect"))
    )
    (net (code "97") (name "unconnected-(U5-T4CLKO_2{slash}PWM8_3{slash}TxD4{slash}ADC11{slash}AD3{slash}P0.3-Pad46)") (class "Default")
      (node (ref "U5") (pin "46") (pinfunction "T4CLKO_2/PWM8_3/TxD4/ADC11/AD3/P0.3_46") (pintype "passive+no_connect"))
    )
    (net (code "98") (name "unconnected-(U5-T4CLKO{slash}AD7{slash}P0.7-Pad4)") (class "Default")
      (node (ref "U5") (pin "4") (pinfunction "T4CLKO/AD7/P0.7_4") (pintype "passive+no_connect"))
    )
    (net (code "99") (name "unconnected-(U5-T4_2{slash}PWM7_3{slash}RxD4{slash}ADC10{slash}AD2{slash}P0.2-Pad45)") (class "Default")
      (node (ref "U5") (pin "45") (pinfunction "T4_2/PWM7_3/RxD4/ADC10/AD2/P0.2_45") (pintype "passive+no_connect"))
    )
    (net (code "100") (name "unconnected-(USB1-1-Pad7)") (class "Default")
      (node (ref "USB1") (pin "7") (pinfunction "1_7") (pintype "passive"))
    )
    (net (code "101") (name "unconnected-(USB1-4-Pad5)") (class "Default")
      (node (ref "USB1") (pin "5") (pinfunction "4_5") (pintype "passive"))
    )
  )
)
